# SH10_-_USB.net
KiCad netlist of a schematic drawn in Altium Designer
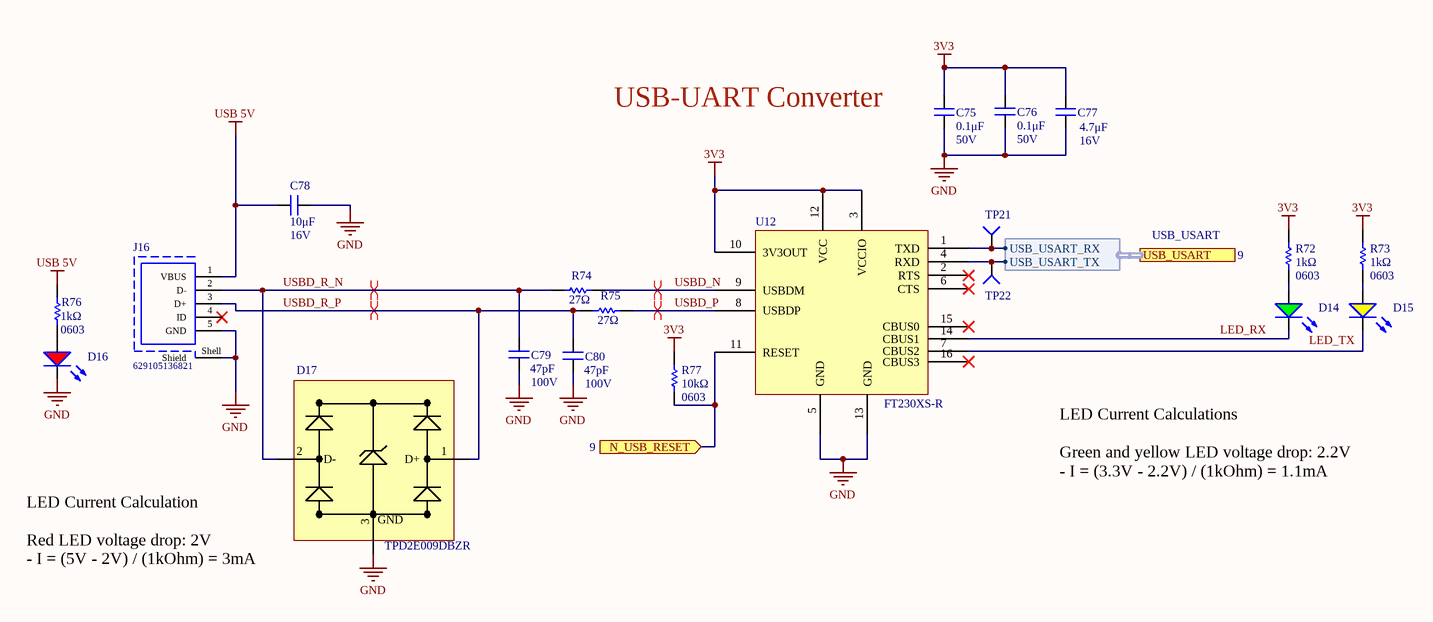
[diagram p0: SH10 - USB.SchDoc]

(export (version "E")
  (design (tool "Eeschema 10.0.6"))
  (components
    (comp (ref "C75")
      (value "0.1μF")
      (footprint "CAP2012")
      (description "CAP CER 0.1UF 50V X7R 0805")
      (fields (field (name "TOLERANCE") "10%") (field (name "VOLTAGE RATING") "50V"))
      (libsource (lib "UWRT_Schematic_Library_2020") (part "CAP_0.1uF_50V_0805"))
    )
    (comp (ref "C76")
      (value "0.1μF")
      (footprint "CAP2012")
      (description "CAP CER 0.1UF 50V X7R 0805")
      (fields (field (name "TOLERANCE") "10%") (field (name "VOLTAGE RATING") "50V"))
      (libsource (lib "UWRT_Schematic_Library_2020") (part "CAP_0.1uF_50V_0805"))
    )
    (comp (ref "C77")
      (value "4.7μF")
      (footprint "CAP0603")
      (description "CAP CER 4.7UF 16V X6S 0603")
      (fields (field (name "VOLTAGE RATING") "16V") (field (name "Comment") "CAP_4.7uF_16V_0603"))
      (libsource (lib "UWRT_Schematic_Library_2020") (part "CAP_4.7uF_16V_0603"))
    )
    (comp (ref "C78")
      (value "10μF")
      (footprint "CAP0603")
      (description "CAP CER 10000PF 16V X7R 0603")
      (fields (field (name "VOLTAGE RATING") "16V") (field (name "Comment") "CAP_10nF_0603"))
      (libsource (lib "UWRT_Schematic_Library_2020") (part "CAP_10nF_0603"))
    )
    (comp (ref "C79")
      (value "47pF")
      (footprint "CAP0603")
      (description "CAP CER 47PF 100V C0G/NP0 0603")
      (fields (field (name "VOLTAGE RATING") "100V") (field (name "Comment") "CAP_47pF_100V_0603"))
      (libsource (lib "UWRT_Schematic_Library_2020") (part "CAP_47pF_100V_0603"))
    )
    (comp (ref "C80")
      (value "47pF")
      (footprint "CAP0603")
      (description "CAP CER 47PF 100V C0G/NP0 0603")
      (fields (field (name "VOLTAGE RATING") "100V") (field (name "Comment") "CAP_47pF_100V_0603"))
      (libsource (lib "UWRT_Schematic_Library_2020") (part "CAP_47pF_100V_0603"))
    )
    (comp (ref "D14")
      (value "LG R971-KN-1")
      (footprint "LED_0805_GREEN")
      (description "LED GREEN DIFFUSED 0805 SMD")
      (libsource (lib "UWRT_Schematic_Library_2020") (part "DIO_LED_G"))
    )
    (comp (ref "D15")
      (value "LY R976-PS-36")
      (footprint "LED_0805_YELLOW")
      (description "LED YELLOW DIFFUSED 0805 SMD")
      (libsource (lib "UWRT_Schematic_Library_2020") (part "DIO_LED_Y"))
    )
    (comp (ref "D16")
      (value "LS R976-NR-1")
      (footprint "LED_0805_RED")
      (description "LED RED DIFFUSED 0805 SMD")
      (libsource (lib "UWRT_Schematic_Library_2020") (part "DIO_LED_R"))
    )
    (comp (ref "D17")
      (value "TVS_DIODE_USB_5.5V")
      (footprint "SOT23-3")
      (description "TVS DIODE 5.5V 8V SOT23-3")
      (fields
        (field (name "MANUFACTURER") "Texas Instruments")
        (field (name "MANUFACTURER PART NUMBER") "TPD2E009DBZR")
      )
      (libsource (lib "UWRT_Schematic_Library_2020") (part "TVS_DIODE_USB_5.5V"))
    )
    (comp (ref "J16")
      (value "629105136821")
      (footprint "629105136821")
      (description "CONN RCPT USB2.0 MICRO B SMD R/A")
      (fields (field (name "MANUFACTURER") "Wurth Elektronik") (field (name "PUBLISHER") "WurthElektronik"))
      (libsource (lib "UWRT_Schematic_Library_2020") (part "WE 629105136821"))
    )
    (comp (ref "R72")
      (value "1kΩ")
      (footprint "RESC0603(1608)_N")
      (description "RES 1K OHM 5% 1/10W 0603")
      (fields
        (field (name "TOLERANCE") "5%")
        (field (name "CASE CODE (IMPERIAL)") "0603")
        (field (name "Comment") "RES_1kΩ_0603")
      )
      (libsource (lib "UWRT_Schematic_Library_2020") (part "RES_1kΩ_0603_5%"))
    )
    (comp (ref "R73")
      (value "1kΩ")
      (footprint "RESC0603(1608)_N")
      (description "RES 1K OHM 5% 1/10W 0603")
      (fields
        (field (name "TOLERANCE") "5%")
        (field (name "CASE CODE (IMPERIAL)") "0603")
        (field (name "Comment") "RES_1kΩ_0603")
      )
      (libsource (lib "UWRT_Schematic_Library_2020") (part "RES_1kΩ_0603_5%"))
    )
    (comp (ref "R74")
      (value "RES_27Ω_0603")
      (footprint "RESC0603(1608)_N")
      (description "RES 27 OHM 5% 1/10W 0603")
      (fields
        (field (name "MANUFACTURER") "Yageo")
        (field (name "TOLERANCE") "5%")
        (field (name "RESISTANCE") "27Ω")
      )
      (libsource (lib "UWRT_Schematic_Library_2020") (part "RES_27Ω_0603_5%"))
    )
    (comp (ref "R75")
      (value "RES_27Ω_0603")
      (footprint "RESC0603(1608)_N")
      (description "RES 27 OHM 5% 1/10W 0603")
      (fields
        (field (name "MANUFACTURER") "Yageo")
        (field (name "TOLERANCE") "5%")
        (field (name "RESISTANCE") "27Ω")
      )
      (libsource (lib "UWRT_Schematic_Library_2020") (part "RES_27Ω_0603_5%"))
    )
    (comp (ref "R76")
      (value "1kΩ")
      (footprint "RESC0603(1608)_N")
      (description "RES 1K OHM 5% 1/10W 0603")
      (fields
        (field (name "TOLERANCE") "5%")
        (field (name "CASE CODE (IMPERIAL)") "0603")
        (field (name "Comment") "RES_1kΩ_0603")
      )
      (libsource (lib "UWRT_Schematic_Library_2020") (part "RES_1kΩ_0603_5%"))
    )
    (comp (ref "R77")
      (value "10kΩ")
      (footprint "RESC0603(1608)_N")
      (description "RES 10K OHM 5% 1/10W 0603")
      (fields
        (field (name "TOLERANCE") "5%")
        (field (name "CASE CODE (IMPERIAL)") "0603")
        (field (name "Comment") "RES_10kΩ_0603")
      )
      (libsource (lib "UWRT_Schematic_Library_2020") (part "RES_10kΩ_0603_5%"))
    )
    (comp (ref "TP21")
      (value "TESTPOINT_SMD_LOOP")
      (footprint "S1751-46R")
      (description "PC TEST POINT SMD")
      (libsource (lib "UWRT_Schematic_Library_2020") (part "TESTPOINT_SMD_LOOP"))
    )
    (comp (ref "TP22")
      (value "TESTPOINT_SMD_LOOP")
      (footprint "S1751-46R")
      (description "PC TEST POINT SMD")
      (libsource (lib "UWRT_Schematic_Library_2020") (part "TESTPOINT_SMD_LOOP"))
    )
    (comp (ref "U12")
      (value "IC_USB_TRANSCEIVER")
      (footprint "SSOP16-0.635-5X4MM")
      (description "IC USB SERIAL BASIC UART 16SSOP")
      (fields (field (name "MANUFACTURER PART NUMBER 1") "FT230XS-R"))
      (libsource (lib "UWRT_Schematic_Library_2020") (part "IC_USB_TRANSCEIVER"))
    )
  )
  (nets
    (net (code "4") (name "/N_USB_RESET") (class "Default")
      (node (ref "R77") (pin "1") (pinfunction "1_1") (pintype "passive"))
      (node (ref "U12") (pin "11") (pinfunction "RESET_11") (pintype "passive"))
    )
    (net (code "5") (name "/USBD_N") (class "Default")
      (node (ref "R74") (pin "2") (pinfunction "2_2") (pintype "passive"))
      (node (ref "U12") (pin "9") (pinfunction "USBDM_9") (pintype "passive"))
    )
    (net (code "6") (name "/USBD_P") (class "Default")
      (node (ref "R75") (pin "2") (pinfunction "2_2") (pintype "passive"))
      (node (ref "U12") (pin "8") (pinfunction "USBDP_8") (pintype "passive"))
    )
    (net (code "7") (name "/USBD_R_N") (class "Default")
      (node (ref "C79") (pin "2") (pinfunction "2_2") (pintype "passive"))
      (node (ref "D17") (pin "2") (pinfunction "D-_2") (pintype "passive"))
      (node (ref "J16") (pin "2") (pinfunction "D-_2") (pintype "passive"))
      (node (ref "R74") (pin "1") (pinfunction "1_1") (pintype "passive"))
    )
    (net (code "8") (name "/USBD_R_P") (class "Default")
      (node (ref "C80") (pin "1") (pinfunction "1_1") (pintype "passive"))
      (node (ref "D17") (pin "1") (pinfunction "D+_1") (pintype "passive"))
      (node (ref "J16") (pin "3") (pinfunction "D+_3") (pintype "passive"))
      (node (ref "R75") (pin "1") (pinfunction "1_1") (pintype "passive"))
    )
    (net (code "10") (name "3V3") (class "Default")
      (node (ref "C75") (pin "2") (pinfunction "2_2") (pintype "passive"))
      (node (ref "C76") (pin "2") (pinfunction "2_2") (pintype "passive"))
      (node (ref "C77") (pin "1") (pinfunction "1_1") (pintype "passive"))
      (node (ref "R72") (pin "2") (pinfunction "2_2") (pintype "passive"))
      (node (ref "R73") (pin "2") (pinfunction "2_2") (pintype "passive"))
      (node (ref "R77") (pin "2") (pinfunction "2_2") (pintype "passive"))
      (node (ref "U12") (pin "10") (pinfunction "3V3OUT_10") (pintype "passive"))
      (node (ref "U12") (pin "12") (pinfunction "VCC_12") (pintype "passive"))
      (node (ref "U12") (pin "3") (pinfunction "VCCIO_3") (pintype "passive"))
    )
    (net (code "11") (name "GND") (class "Default")
      (node (ref "C75") (pin "1") (pinfunction "1_1") (pintype "passive"))
      (node (ref "C76") (pin "1") (pinfunction "1_1") (pintype "passive"))
      (node (ref "C77") (pin "2") (pinfunction "2_2") (pintype "passive"))
      (node (ref "C78") (pin "2") (pinfunction "2_2") (pintype "passive"))
      (node (ref "C79") (pin "1") (pinfunction "1_1") (pintype "passive"))
      (node (ref "C80") (pin "2") (pinfunction "2_2") (pintype "passive"))
      (node (ref "D16") (pin "2") (pinfunction "K_2") (pintype "passive"))
      (node (ref "D17") (pin "3") (pinfunction "GND_3") (pintype "passive"))
      (node (ref "J16") (pin "5") (pinfunction "GND_5") (pintype "passive"))
      (node (ref "J16") (pin "Shell") (pinfunction "Shield_Shell") (pintype "passive"))
      (node (ref "U12") (pin "13") (pinfunction "GND_13") (pintype "passive"))
      (node (ref "U12") (pin "5") (pinfunction "GND_5") (pintype "passive"))
    )
    (net (code "12") (name "Net-(D14-A)") (class "Default")
      (node (ref "D14") (pin "1") (pinfunction "A_1") (pintype "passive"))
      (node (ref "R72") (pin "1") (pinfunction "1_1") (pintype "passive"))
    )
    (net (code "13") (name "Net-(D14-K)") (class "Default")
      (node (ref "D14") (pin "2") (pinfunction "K_2") (pintype "passive"))
      (node (ref "U12") (pin "14") (pinfunction "CBUS1_14") (pintype "passive"))
    )
    (net (code "14") (name "Net-(D15-A)") (class "Default")
      (node (ref "D15") (pin "1") (pinfunction "A_1") (pintype "passive"))
      (node (ref "R73") (pin "1") (pinfunction "1_1") (pintype "passive"))
    )
    (net (code "15") (name "Net-(D15-K)") (class "Default")
      (node (ref "D15") (pin "2") (pinfunction "K_2") (pintype "passive"))
      (node (ref "U12") (pin "7") (pinfunction "CBUS2_7") (pintype "passive"))
    )
    (net (code "16") (name "Net-(D16-A)") (class "Default")
      (node (ref "D16") (pin "1") (pinfunction "A_1") (pintype "passive"))
      (node (ref "R76") (pin "1") (pinfunction "1_1") (pintype "passive"))
    )
    (net (code "17") (name "Net-(TP21-=value)") (class "Default")
      (node (ref "TP21") (pin "1") (pinfunction "=value_1") (pintype "passive"))
      (node (ref "U12") (pin "1") (pinfunction "TXD_1") (pintype "passive"))
    )
    (net (code "18") (name "Net-(TP22-=value)") (class "Default")
      (node (ref "TP22") (pin "1") (pinfunction "=value_1") (pintype "passive"))
      (node (ref "U12") (pin "4") (pinfunction "RXD_4") (pintype "passive"))
    )
    (net (code "19") (name "USB 5V") (class "Default")
      (node (ref "C78") (pin "1") (pinfunction "1_1") (pintype "passive"))
      (node (ref "J16") (pin "1") (pinfunction "VBUS_1") (pintype "passive"))
      (node (ref "R76") (pin "2") (pinfunction "2_2") (pintype "passive"))
    )
    (net (code "20") (name "unconnected-(J16-ID-Pad4)") (class "Default")
      (node (ref "J16") (pin "4") (pinfunction "ID_4") (pintype "passive+no_connect"))
    )
    (net (code "21") (name "unconnected-(U12-CBUS0-Pad15)") (class "Default")
      (node (ref "U12") (pin "15") (pinfunction "CBUS0_15") (pintype "passive+no_connect"))
    )
    (net (code "22") (name "unconnected-(U12-CBUS3-Pad16)") (class "Default")
      (node (ref "U12") (pin "16") (pinfunction "CBUS3_16") (pintype "passive+no_connect"))
    )
    (net (code "23") (name "unconnected-(U12-CTS-Pad6)") (class "Default")
      (node (ref "U12") (pin "6") (pinfunction "CTS_6") (pintype "passive+no_connect"))
    )
    (net (code "24") (name "unconnected-(U12-RTS-Pad2)") (class "Default")
      (node (ref "U12") (pin "2") (pinfunction "RTS_2") (pintype "passive+no_connect"))
    )
  )
)
